# SIM800C_SCH.net
KiCad netlist of a schematic drawn in Altium Designer
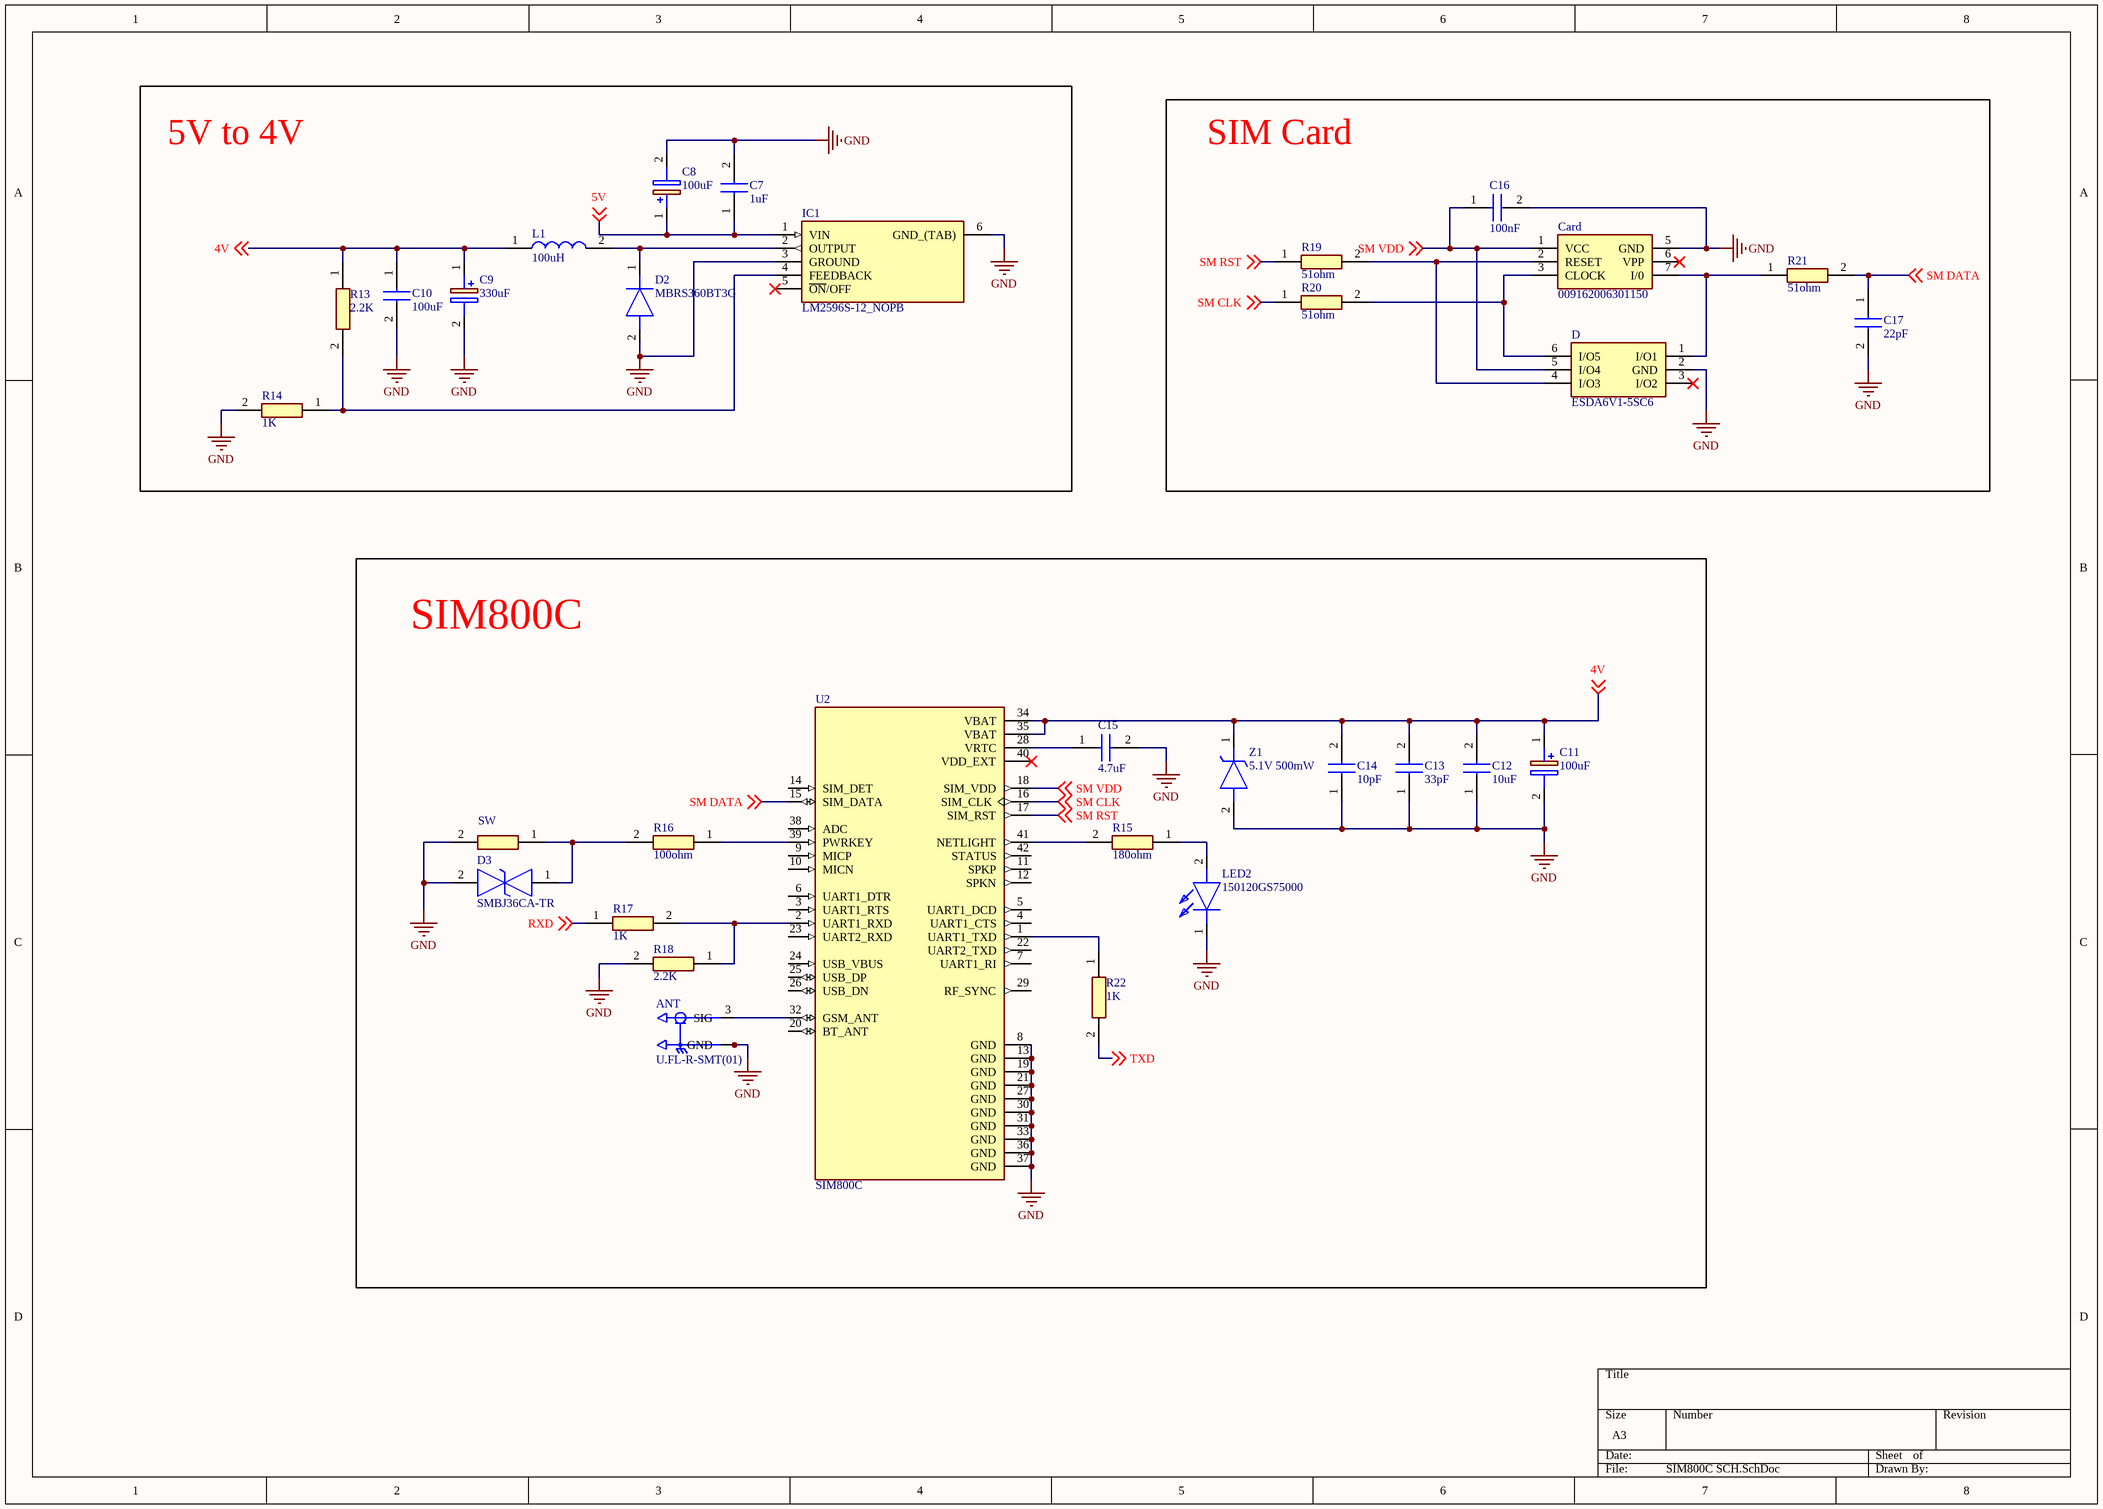
[diagram p0: SIM800C SCH.SchDoc]

(export (version "E")
  (design (tool "Eeschema 10.0.6"))
  (components
    (comp (ref "ANT")
      (value "U.FL-R-SMT(01)")
      (footprint "HRS_U.FL-R-SMT(01)")
      (fields (field (name "MF") "Hirose"))
      (libsource (lib "U.FL-R-SMT_01_") (part "U.FL-R-SMT(01)"))
    )
    (comp (ref "C7")
      (value "1uF")
      (footprint "SamacSys:CAPC3216X127N")
      (description "Capacitor")
      (fields
        (field (name "MANUFACTURER_PART_NUMBER") "1206YC105JAT2A")
        (field (name "MOUSER PART NUMBER") "581-1206YC105J")
      )
      (libsource (lib "SamacSys") (part "1206YC105JAT2A"))
    )
    (comp (ref "C8")
      (value "100uF")
      (footprint "SamacSys:CAPAE660X800N")
      (description "100uF 25VDC 20% Capacitor Polarised")
      (fields
        (field (name "MANUFACTURER_PART_NUMBER") "EEV107M025A9HAA")
        (field (name "MOUSER PART NUMBER") "80-EEV107M025A9HAA")
      )
      (libsource (lib "SamacSys") (part "EEV107M025A9HAA"))
    )
    (comp (ref "C9")
      (value "330uF")
      (footprint "SamacSys:EEETC1V470P")
      (description "330uF 20% tolerance 25VDC Capacitor Polarised")
      (fields (field (name "MANUFACTURER_PART_NUMBER") "EEE-FH1E331UL"))
      (libsource (lib "SamacSys") (part "EEE-FH1E331UL"))
    )
    (comp (ref "C10")
      (value "100uF")
      (footprint "SamacSys:CAPC3216X127N")
      (description "100uF 10% tolerance 10VDC Capacitor")
      (fields
        (field (name "MANUFACTURER_PART_NUMBER") "1206YC105JAT2A")
        (field (name "MOUSER PART NUMBER") "581-1206YC105J")
      )
      (libsource (lib "SamacSys") (part "1206YC105JAT2A"))
    )
    (comp (ref "C11")
      (value "100uF")
      (footprint "SamacSys:T510E")
      (description "100uF 25VDC Capacitor Polarised")
      (fields
        (field (name "MANUFACTURER_PART_NUMBER") "T510E107M025ATE050")
        (field (name "MOUSER PART NUMBER") "80-T510E107M025")
      )
      (libsource (lib "SamacSys") (part "T510E107M025ATE050"))
    )
    (comp (ref "C12")
      (value "10uF")
      (footprint "SamacSys:CAPC3216X127N")
      (description "10uF 25VDC Capacitor")
      (fields
        (field (name "MANUFACTURER_PART_NUMBER") "1206YC105JAT2A")
        (field (name "MOUSER PART NUMBER") "581-1206YC105J")
      )
      (libsource (lib "SamacSys") (part "1206YC105JAT2A"))
    )
    (comp (ref "C13")
      (value "33pF")
      (footprint "SamacSys:CAPC3216X127N")
      (description "33pF 50VDC Capacitor")
      (fields
        (field (name "MANUFACTURER_PART_NUMBER") "1206YC105JAT2A")
        (field (name "MOUSER PART NUMBER") "581-1206YC105J")
      )
      (libsource (lib "SamacSys") (part "1206YC105JAT2A"))
    )
    (comp (ref "C14")
      (value "10pF")
      (footprint "SamacSys:CAPC3216X127N")
      (description "10pF 50VDC Capacitor")
      (fields
        (field (name "MANUFACTURER_PART_NUMBER") "1206YC105JAT2A")
        (field (name "MOUSER PART NUMBER") "581-1206YC105J")
      )
      (libsource (lib "SamacSys") (part "1206YC105JAT2A"))
    )
    (comp (ref "C15")
      (value "4.7uF")
      (footprint "SamacSys:CAPC3216X127N")
      (description "Capacitor")
      (fields
        (field (name "MANUFACTURER_PART_NUMBER") "1206YC105JAT2A")
        (field (name "MOUSER PART NUMBER") "581-1206YC105J")
      )
      (libsource (lib "SamacSys") (part "1206YC105JAT2A"))
    )
    (comp (ref "C16")
      (value "100nF")
      (footprint "SamacSys:CAPC3216X127N")
      (description "100nF 10% tolerance 50VDC Capacitor")
      (fields
        (field (name "MANUFACTURER_PART_NUMBER") "1206YC105JAT2A")
        (field (name "MOUSER PART NUMBER") "581-1206YC105J")
      )
      (libsource (lib "SamacSys") (part "1206YC105JAT2A"))
    )
    (comp (ref "C17")
      (value "22pF")
      (footprint "SamacSys:CAPC3216X170N")
      (description "22pF 10% tolerance 50VDC tolerance Capacitor")
      (fields
        (field (name "MANUFACTURER_PART_NUMBER") "VJ1206A220JXGAT5Z")
        (field (name "MOUSER PART NUMBER") "77-VJ1206A220JXGAT5Z")
      )
      (libsource (lib "SamacSys") (part "VJ1206A220JXGAT5Z"))
    )
    (comp (ref "Card")
      (value "009162006301150")
      (footprint "SamacSys:009162006301150")
      (description "Connector")
      (fields (field (name "MOUSER PART NUMBER") "581-009162006301150"))
      (libsource (lib "SamacSys") (part "009162006301150"))
    )
    (comp (ref "D")
      (value "ESDA6V1-5SC6")
      (footprint "SamacSys:SOT95P280X145-6N")
      (description "Integrated Circuit")
      (fields (field (name "MOUSER PART NUMBER") "511-ESDA6V1-5SC6"))
      (libsource (lib "SamacSys") (part "ESDA6V1-5SC6"))
    )
    (comp (ref "D2")
      (value "MBRS360BT3G")
      (footprint "SamacSys:DIOM5436X247N")
      (description "Schottky Diodes & Rectifiers 60V,Schottky,SMA,3A")
      (fields (field (name "MOUSER PART NUMBER") "863-MBRS360BT3G"))
      (libsource (lib "SamacSys") (part "MBRS360BT3G"))
    )
    (comp (ref "D3")
      (value "SMBJ36CA-TR")
      (footprint "SamacSys:SMBJ50CA")
      (description "TVS Diode (Bi-directional) - SMBJ22A")
      (fields (field (name "MOUSER PART NUMBER") "511-SMBJ36CA-TR"))
      (libsource (lib "SamacSys") (part "SMBJ36CA-TR"))
    )
    (comp (ref "IC1")
      (value "LM2596S-12_NOPB")
      (footprint "SamacSys:TO170P1435X465-6N")
      (description "Integrated Circuit")
      (fields
        (field (name "MANUFACTURER_PART_NUMBER") "LM2596S-12/NOPB")
        (field (name "MOUSER PART NUMBER") "926-LM2596S-12/NOPB")
      )
      (libsource (lib "SamacSys") (part "LM2596S-12_NOPB"))
    )
    (comp (ref "L1")
      (value "100uH")
      (footprint "SamacSys:RLH0912101KL")
      (description "100uH 10% tolerance 900mA Inductor")
      (fields
        (field (name "MANUFACTURER_PART_NUMBER") "RLH0912-101KL")
        (field (name "MOUSER PART NUMBER") "652-RLH0912-101KL")
      )
      (libsource (lib "SamacSys") (part "RLH0912-101KL"))
    )
    (comp (ref "LED2")
      (value "150120GS75000")
      (footprint "SamacSys:LEDC3214X78N")
      (description "LED")
      (fields (field (name "MOUSER PART NUMBER") "710-150120GS75000"))
      (libsource (lib "SamacSys") (part "150120GS75000"))
    )
    (comp (ref "R13")
      (value "2.2K")
      (footprint "SamacSys:RESC3216X51N")
      (description "2.2K 1% tolerance Resistor")
      (fields
        (field (name "MANUFACTURER_PART_NUMBER") "PHPA1206E1001BST1")
        (field (name "MOUSER PART NUMBER") "71-PHPA1206E1001BST1")
      )
      (libsource (lib "") (part "PHPA1206E1001BST1_2"))
    )
    (comp (ref "R14")
      (value "1K")
      (footprint "SamacSys:RESC3216X51N")
      (description "1K 1% tolerance Resistor")
      (fields
        (field (name "MANUFACTURER_PART_NUMBER") "PHPA1206E1001BST1")
        (field (name "MOUSER PART NUMBER") "71-PHPA1206E1001BST1")
      )
      (libsource (lib "SamacSys") (part "PHPA1206E1001BST1"))
    )
    (comp (ref "R15")
      (value "180ohm")
      (footprint "SamacSys:RESC3216X51N")
      (description "180ohm 1% tolerance Resistor")
      (fields
        (field (name "MANUFACTURER_PART_NUMBER") "PHPA1206E1001BST1")
        (field (name "MOUSER PART NUMBER") "71-PHPA1206E1001BST1")
      )
      (libsource (lib "SamacSys") (part "PHPA1206E1001BST1"))
    )
    (comp (ref "R16")
      (value "100ohm")
      (footprint "SamacSys:RESC3216X51N")
      (description "100ohm 1% tolerance Resistor")
      (fields
        (field (name "MANUFACTURER_PART_NUMBER") "PHPA1206E1001BST1")
        (field (name "MOUSER PART NUMBER") "71-PHPA1206E1001BST1")
      )
      (libsource (lib "SamacSys") (part "PHPA1206E1001BST1"))
    )
    (comp (ref "R17")
      (value "1K")
      (footprint "SamacSys:RESC3216X51N")
      (description "1K 1% tolerance Resistor")
      (fields
        (field (name "MANUFACTURER_PART_NUMBER") "PHPA1206E1001BST1")
        (field (name "MOUSER PART NUMBER") "71-PHPA1206E1001BST1")
      )
      (libsource (lib "") (part "PHPA1206E1001BST1_1"))
    )
    (comp (ref "R18")
      (value "2.2K")
      (footprint "SamacSys:RESC3216X51N")
      (description "2.2K 1% tolerance Resistor")
      (fields
        (field (name "MANUFACTURER_PART_NUMBER") "PHPA1206E1001BST1")
        (field (name "MOUSER PART NUMBER") "71-PHPA1206E1001BST1")
      )
      (libsource (lib "SamacSys") (part "PHPA1206E1001BST1"))
    )
    (comp (ref "R19")
      (value "51ohm")
      (footprint "SamacSys:RESC3216X60N")
      (description "51ohm 1% tolerance Resistor")
      (fields
        (field (name "MANUFACTURER_PART_NUMBER") "CRCW120651R0FKEAC")
        (field (name "MOUSER PART NUMBER") "71-CRCW120651R0FKEAC")
      )
      (libsource (lib "SamacSys") (part "CRCW120651R0FKEAC"))
    )
    (comp (ref "R20")
      (value "51ohm")
      (footprint "SamacSys:RESC3216X60N")
      (description "51ohm 1% tolerance Resistor")
      (fields
        (field (name "MANUFACTURER_PART_NUMBER") "CRCW120651R0FKEAC")
        (field (name "MOUSER PART NUMBER") "71-CRCW120651R0FKEAC")
      )
      (libsource (lib "SamacSys") (part "CRCW120651R0FKEAC"))
    )
    (comp (ref "R21")
      (value "51ohm")
      (footprint "SamacSys:RESC3216X60N")
      (description "51ohm 1% tolerance Resistor")
      (fields
        (field (name "MANUFACTURER_PART_NUMBER") "CRCW120651R0FKEAC")
        (field (name "MOUSER PART NUMBER") "71-CRCW120651R0FKEAC")
      )
      (libsource (lib "SamacSys") (part "CRCW120651R0FKEAC"))
    )
    (comp (ref "R22")
      (value "1K")
      (footprint "SamacSys:RESC3216X51N")
      (description "1K 1% tolerance Resistor")
      (fields
        (field (name "MANUFACTURER_PART_NUMBER") "PHPA1206E1001BST1")
        (field (name "MOUSER PART NUMBER") "71-PHPA1206E1001BST1")
      )
      (libsource (lib "") (part "PHPA1206E1001BST1_2"))
    )
    (comp (ref "SW")
      (value "PHPA1206E1001BST1")
      (footprint "SamacSys:RESC3216X51N")
      (description "2 Pin switch")
      (fields (field (name "MOUSER PART NUMBER") "71-PHPA1206E1001BST1"))
      (libsource (lib "SamacSys") (part "PHPA1206E1001BST1"))
    )
    (comp (ref "U2")
      (value "SIM800C")
      (footprint "LCC110P1570X1760X250-42N")
      (description "Module: GSM/Bluetooth; GPRS; 2G; 1800MHz, 900MHz; 85.6kbps; SMD")
      (fields (field (name "MF") "Simcom"))
      (libsource (lib "SIM800C") (part "SIM800C"))
    )
    (comp (ref "Z1")
      (value "5.1V 500mW")
      (footprint "SamacSys:SOD3716X135N")
      (description "Zener Diode 5.1V 500mW")
      (fields
        (field (name "MANUFACTURER_PART_NUMBER") "MMSZ5231C-E3-08")
        (field (name "MOUSER PART NUMBER") "78-MMSZ5231C-E3-08")
      )
      (libsource (lib "SamacSys") (part "MMSZ5231C-E3-08"))
    )
  )
  (nets
    (net (code "1") (name "4V") (class "Default")
      (node (ref "C10") (pin "1") (pinfunction "1_1") (pintype "passive"))
      (node (ref "C11") (pin "1") (pinfunction "+_1") (pintype "passive"))
      (node (ref "C12") (pin "2") (pinfunction "2_2") (pintype "passive"))
      (node (ref "C13") (pin "2") (pinfunction "2_2") (pintype "passive"))
      (node (ref "C14") (pin "2") (pinfunction "2_2") (pintype "passive"))
      (node (ref "C9") (pin "1") (pinfunction "+_1") (pintype "passive"))
      (node (ref "L1") (pin "1") (pinfunction "1_1") (pintype "passive"))
      (node (ref "R13") (pin "1") (pinfunction "1_1") (pintype "passive"))
      (node (ref "U2") (pin "34") (pinfunction "VBAT_34") (pintype "power_in"))
      (node (ref "U2") (pin "35") (pinfunction "VBAT_35") (pintype "power_in"))
      (node (ref "Z1") (pin "1") (pinfunction "K_1") (pintype "power_in"))
    )
    (net (code "2") (name "5V") (class "Default")
      (node (ref "C7") (pin "1") (pinfunction "1_1") (pintype "passive"))
      (node (ref "C8") (pin "1") (pinfunction "+_1") (pintype "passive"))
      (node (ref "IC1") (pin "1") (pinfunction "VIN_1") (pintype "input"))
    )
    (net (code "3") (name "GND") (class "Default")
      (node (ref "ANT") (pin "1") (pinfunction "GND_1") (pintype "passive"))
      (node (ref "ANT") (pin "2") (pinfunction "GND_2") (pintype "passive"))
      (node (ref "C10") (pin "2") (pinfunction "2_2") (pintype "passive"))
      (node (ref "C11") (pin "2") (pinfunction "-_2") (pintype "passive"))
      (node (ref "C12") (pin "1") (pinfunction "1_1") (pintype "passive"))
      (node (ref "C13") (pin "1") (pinfunction "1_1") (pintype "passive"))
      (node (ref "C14") (pin "1") (pinfunction "1_1") (pintype "passive"))
      (node (ref "C15") (pin "2") (pinfunction "2_2") (pintype "passive"))
      (node (ref "C16") (pin "2") (pinfunction "2_2") (pintype "passive"))
      (node (ref "C17") (pin "2") (pinfunction "2_2") (pintype "passive"))
      (node (ref "C7") (pin "2") (pinfunction "2_2") (pintype "passive"))
      (node (ref "C8") (pin "2") (pinfunction "-_2") (pintype "passive"))
      (node (ref "C9") (pin "2") (pinfunction "-_2") (pintype "passive"))
      (node (ref "Card") (pin "5") (pinfunction "GND_5") (pintype "passive"))
      (node (ref "D") (pin "2") (pinfunction "GND_2") (pintype "passive"))
      (node (ref "D2") (pin "2") (pinfunction "A_2") (pintype "passive"))
      (node (ref "D3") (pin "2") (pinfunction "2_2") (pintype "passive"))
      (node (ref "IC1") (pin "3") (pinfunction "GROUND_3") (pintype "passive"))
      (node (ref "IC1") (pin "6") (pinfunction "GND_(TAB)_6") (pintype "power_in"))
      (node (ref "LED2") (pin "1") (pinfunction "K_1") (pintype "passive"))
      (node (ref "R14") (pin "2") (pinfunction "2_2") (pintype "passive"))
      (node (ref "R18") (pin "2") (pinfunction "2_2") (pintype "passive"))
      (node (ref "SW") (pin "2") (pinfunction "2_2") (pintype "passive"))
      (node (ref "U2") (pin "13") (pinfunction "GND_13") (pintype "power_in"))
      (node (ref "U2") (pin "19") (pinfunction "GND_19") (pintype "power_in"))
      (node (ref "U2") (pin "21") (pinfunction "GND_21") (pintype "power_in"))
      (node (ref "U2") (pin "27") (pinfunction "GND_27") (pintype "power_in"))
      (node (ref "U2") (pin "30") (pinfunction "GND_30") (pintype "power_in"))
      (node (ref "U2") (pin "31") (pinfunction "GND_31") (pintype "power_in"))
      (node (ref "U2") (pin "33") (pinfunction "GND_33") (pintype "power_in"))
      (node (ref "U2") (pin "36") (pinfunction "GND_36") (pintype "power_in"))
      (node (ref "U2") (pin "37") (pinfunction "GND_37") (pintype "power_in"))
      (node (ref "U2") (pin "8") (pinfunction "GND_8") (pintype "power_in"))
      (node (ref "Z1") (pin "2") (pinfunction "A_2") (pintype "power_in"))
    )
    (net (code "4") (name "Net-(ANT-SIG)") (class "Default")
      (node (ref "ANT") (pin "3") (pinfunction "SIG_3") (pintype "passive"))
      (node (ref "U2") (pin "32") (pinfunction "GSM_ANT_32") (pintype "bidirectional"))
    )
    (net (code "5") (name "Net-(Card-CLOCK)") (class "Default")
      (node (ref "Card") (pin "3") (pinfunction "CLOCK_3") (pintype "passive"))
      (node (ref "D") (pin "6") (pinfunction "I/O5_6") (pintype "passive"))
      (node (ref "R20") (pin "2") (pinfunction "2_2") (pintype "passive"))
    )
    (net (code "6") (name "Net-(Card-I{slash}0)") (class "Default")
      (node (ref "Card") (pin "7") (pinfunction "I/0_7") (pintype "passive"))
      (node (ref "D") (pin "1") (pinfunction "I/O1_1") (pintype "passive"))
      (node (ref "R21") (pin "1") (pinfunction "1_1") (pintype "passive"))
    )
    (net (code "7") (name "Net-(Card-RESET)") (class "Default")
      (node (ref "Card") (pin "2") (pinfunction "RESET_2") (pintype "passive"))
      (node (ref "D") (pin "4") (pinfunction "I/O3_4") (pintype "passive"))
      (node (ref "R19") (pin "2") (pinfunction "2_2") (pintype "passive"))
    )
    (net (code "8") (name "Net-(D2-K)") (class "Default")
      (node (ref "D2") (pin "1") (pinfunction "K_1") (pintype "passive"))
      (node (ref "IC1") (pin "2") (pinfunction "OUTPUT_2") (pintype "output"))
      (node (ref "L1") (pin "2") (pinfunction "2_2") (pintype "passive"))
    )
    (net (code "9") (name "Net-(D3-Pad1)") (class "Default")
      (node (ref "D3") (pin "1") (pinfunction "1_1") (pintype "passive"))
      (node (ref "R16") (pin "2") (pinfunction "2_2") (pintype "passive"))
      (node (ref "SW") (pin "1") (pinfunction "1_1") (pintype "passive"))
    )
    (net (code "10") (name "Net-(IC1-FEEDBACK)") (class "Default")
      (node (ref "IC1") (pin "4") (pinfunction "FEEDBACK_4") (pintype "passive"))
      (node (ref "R13") (pin "2") (pinfunction "2_2") (pintype "passive"))
      (node (ref "R14") (pin "1") (pinfunction "1_1") (pintype "passive"))
    )
    (net (code "11") (name "Net-(LED2-A)") (class "Default")
      (node (ref "LED2") (pin "2") (pinfunction "A_2") (pintype "passive"))
      (node (ref "R15") (pin "1") (pinfunction "1_1") (pintype "passive"))
    )
    (net (code "12") (name "Net-(U2-NETLIGHT)") (class "Default")
      (node (ref "R15") (pin "2") (pinfunction "2_2") (pintype "passive"))
      (node (ref "U2") (pin "41") (pinfunction "NETLIGHT_41") (pintype "output"))
    )
    (net (code "13") (name "Net-(U2-PWRKEY)") (class "Default")
      (node (ref "R16") (pin "1") (pinfunction "1_1") (pintype "passive"))
      (node (ref "U2") (pin "39") (pinfunction "PWRKEY_39") (pintype "input"))
    )
    (net (code "14") (name "Net-(U2-UART1_RXD)") (class "Default")
      (node (ref "R17") (pin "2") (pinfunction "2_2") (pintype "passive"))
      (node (ref "R18") (pin "1") (pinfunction "1_1") (pintype "passive"))
      (node (ref "U2") (pin "2") (pinfunction "UART1_RXD_2") (pintype "input"))
    )
    (net (code "15") (name "Net-(U2-UART1_TXD)") (class "Default")
      (node (ref "R22") (pin "1") (pinfunction "1_1") (pintype "passive"))
      (node (ref "U2") (pin "1") (pinfunction "UART1_TXD_1") (pintype "output"))
    )
    (net (code "16") (name "Net-(U2-VRTC)") (class "Default")
      (node (ref "C15") (pin "1") (pinfunction "1_1") (pintype "passive"))
      (node (ref "U2") (pin "28") (pinfunction "VRTC_28") (pintype "power_in"))
    )
    (net (code "17") (name "RXD") (class "Default")
      (node (ref "R17") (pin "1") (pinfunction "1_1") (pintype "passive"))
    )
    (net (code "18") (name "SM CLK") (class "Default")
      (node (ref "R20") (pin "1") (pinfunction "1_1") (pintype "passive"))
      (node (ref "U2") (pin "16") (pinfunction "SIM_CLK_16") (pintype "output"))
    )
    (net (code "19") (name "SM DATA") (class "Default")
      (node (ref "C17") (pin "1") (pinfunction "1_1") (pintype "passive"))
      (node (ref "R21") (pin "2") (pinfunction "2_2") (pintype "passive"))
      (node (ref "U2") (pin "15") (pinfunction "SIM_DATA_15") (pintype "bidirectional"))
    )
    (net (code "20") (name "SM RST") (class "Default")
      (node (ref "R19") (pin "1") (pinfunction "1_1") (pintype "passive"))
      (node (ref "U2") (pin "17") (pinfunction "SIM_RST_17") (pintype "output"))
    )
    (net (code "21") (name "SM VDD") (class "Default")
      (node (ref "C16") (pin "1") (pinfunction "1_1") (pintype "passive"))
      (node (ref "Card") (pin "1") (pinfunction "VCC_1") (pintype "passive"))
      (node (ref "D") (pin "5") (pinfunction "I/O4_5") (pintype "passive"))
      (node (ref "U2") (pin "18") (pinfunction "SIM_VDD_18") (pintype "output"))
    )
    (net (code "22") (name "TXD") (class "Default")
      (node (ref "R22") (pin "2") (pinfunction "2_2") (pintype "passive"))
    )
    (net (code "23") (name "unconnected-(Card-VPP-Pad6)") (class "Default")
      (node (ref "Card") (pin "6") (pinfunction "VPP_6") (pintype "passive+no_connect"))
    )
    (net (code "24") (name "unconnected-(D-I{slash}O2-Pad3)") (class "Default")
      (node (ref "D") (pin "3") (pinfunction "I/O2_3") (pintype "passive+no_connect"))
    )
    (net (code "25") (name "unconnected-(IC1-~{ON}{slash}OFF-Pad5)") (class "Default")
      (node (ref "IC1") (pin "5") (pinfunction "~{ON}/OFF_5") (pintype "passive+no_connect"))
    )
    (net (code "26") (name "unconnected-(U2-ADC-Pad38)") (class "Default")
      (node (ref "U2") (pin "38") (pinfunction "ADC_38") (pintype "input"))
    )
    (net (code "27") (name "unconnected-(U2-BT_ANT-Pad20)") (class "Default")
      (node (ref "U2") (pin "20") (pinfunction "BT_ANT_20") (pintype "bidirectional"))
    )
    (net (code "28") (name "unconnected-(U2-MICN-Pad10)") (class "Default")
      (node (ref "U2") (pin "10") (pinfunction "MICN_10") (pintype "input"))
    )
    (net (code "29") (name "unconnected-(U2-MICP-Pad9)") (class "Default")
      (node (ref "U2") (pin "9") (pinfunction "MICP_9") (pintype "input"))
    )
    (net (code "30") (name "unconnected-(U2-RF_SYNC-Pad29)") (class "Default")
      (node (ref "U2") (pin "29") (pinfunction "RF_SYNC_29") (pintype "output"))
    )
    (net (code "31") (name "unconnected-(U2-SIM_DET-Pad14)") (class "Default")
      (node (ref "U2") (pin "14") (pinfunction "SIM_DET_14") (pintype "input"))
    )
    (net (code "32") (name "unconnected-(U2-SPKN-Pad12)") (class "Default")
      (node (ref "U2") (pin "12") (pinfunction "SPKN_12") (pintype "output"))
    )
    (net (code "33") (name "unconnected-(U2-SPKP-Pad11)") (class "Default")
      (node (ref "U2") (pin "11") (pinfunction "SPKP_11") (pintype "output"))
    )
    (net (code "34") (name "unconnected-(U2-STATUS-Pad42)") (class "Default")
      (node (ref "U2") (pin "42") (pinfunction "STATUS_42") (pintype "output"))
    )
    (net (code "35") (name "unconnected-(U2-UART1_CTS-Pad4)") (class "Default")
      (node (ref "U2") (pin "4") (pinfunction "UART1_CTS_4") (pintype "output"))
    )
    (net (code "36") (name "unconnected-(U2-UART1_DCD-Pad5)") (class "Default")
      (node (ref "U2") (pin "5") (pinfunction "UART1_DCD_5") (pintype "output"))
    )
    (net (code "37") (name "unconnected-(U2-UART1_DTR-Pad6)") (class "Default")
      (node (ref "U2") (pin "6") (pinfunction "UART1_DTR_6") (pintype "input"))
    )
    (net (code "38") (name "unconnected-(U2-UART1_RI-Pad7)") (class "Default")
      (node (ref "U2") (pin "7") (pinfunction "UART1_RI_7") (pintype "output"))
    )
    (net (code "39") (name "unconnected-(U2-UART1_RTS-Pad3)") (class "Default")
      (node (ref "U2") (pin "3") (pinfunction "UART1_RTS_3") (pintype "input"))
    )
    (net (code "40") (name "unconnected-(U2-UART2_RXD-Pad23)") (class "Default")
      (node (ref "U2") (pin "23") (pinfunction "UART2_RXD_23") (pintype "input"))
    )
    (net (code "41") (name "unconnected-(U2-UART2_TXD-Pad22)") (class "Default")
      (node (ref "U2") (pin "22") (pinfunction "UART2_TXD_22") (pintype "output"))
    )
    (net (code "42") (name "unconnected-(U2-USB_DN-Pad26)") (class "Default")
      (node (ref "U2") (pin "26") (pinfunction "USB_DN_26") (pintype "bidirectional"))
    )
    (net (code "43") (name "unconnected-(U2-USB_DP-Pad25)") (class "Default")
      (node (ref "U2") (pin "25") (pinfunction "USB_DP_25") (pintype "bidirectional"))
    )
    (net (code "44") (name "unconnected-(U2-USB_VBUS-Pad24)") (class "Default")
      (node (ref "U2") (pin "24") (pinfunction "USB_VBUS_24") (pintype "input"))
    )
    (net (code "45") (name "unconnected-(U2-VDD_EXT-Pad40)") (class "Default")
      (node (ref "U2") (pin "40") (pinfunction "VDD_EXT_40") (pintype "power_in+no_connect"))
    )
  )
)
